# nutzen_03.net
KiCad netlist of a schematic drawn in EAGLE
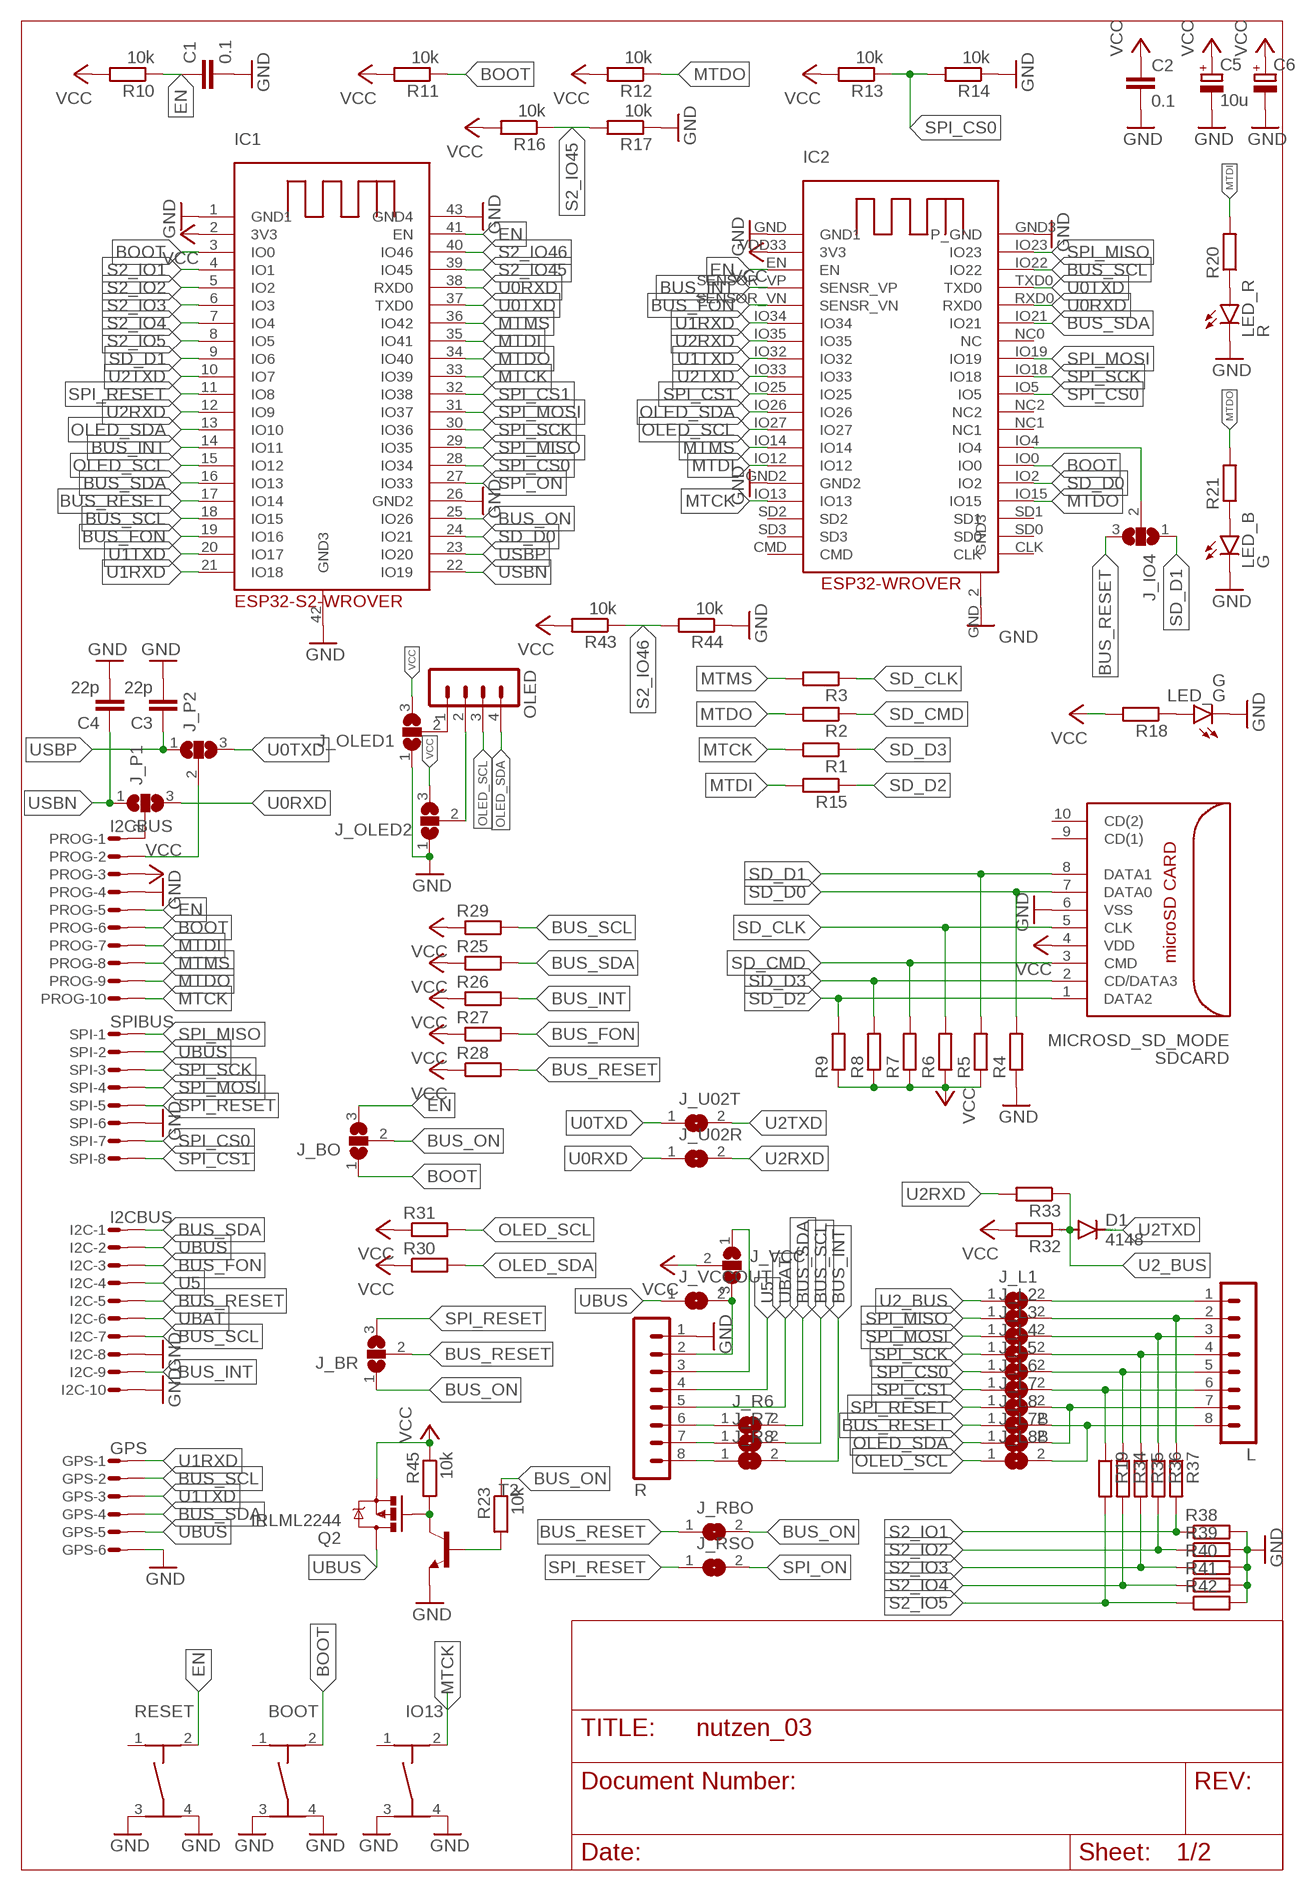
[diagram p0: schematic, sheet 1]

(export (version "E")
  (design (tool "Eeschema 10.0.6"))
  (components
    (comp (ref "BOOT")
      (value "TASTER-9314_SMD")
      (footprint "eagle-import:TASTER-9314_SMD")
      (libsource (lib "eagle-import") (part "TASTER-9314_SMD"))
    )
    (comp (ref "C1")
      (value "0.1")
      (footprint "eagle-import:C0805")
      (libsource (lib "eagle-import") (part "C-EUC0805"))
    )
    (comp (ref "C2")
      (value "0.1")
      (footprint "eagle-import:C0805")
      (libsource (lib "eagle-import") (part "C-EUC0805"))
    )
    (comp (ref "C3")
      (value "22p")
      (footprint "eagle-import:C0805")
      (libsource (lib "eagle-import") (part "C-EUC0805"))
    )
    (comp (ref "C4")
      (value "22p")
      (footprint "eagle-import:C0805")
      (libsource (lib "eagle-import") (part "C-EUC0805"))
    )
    (comp (ref "C5")
      (value "10u")
      (footprint "eagle-import:B_3528-21W")
      (libsource (lib "eagle-import") (part "CPOL-EUB/3528-21W"))
    )
    (comp (ref "C6")
      (value "CPOL-EUC/6032-28R")
      (footprint "eagle-import:C_6032-28R")
      (libsource (lib "eagle-import") (part "CPOL-EUC/6032-28R"))
    )
    (comp (ref "D1")
      (value "4148")
      (footprint "eagle-import:MINIMELF")
      (libsource (lib "eagle-import") (part "DIODE-MINIMELF"))
    )
    (comp (ref "GPS")
      (value "GPS")
      (footprint "eagle-import:MICROMATCH-6SMD")
      (libsource (lib "eagle-import") (part "MICROMATCH-6SMD"))
    )
    (comp (ref "I2C")
      (value "I2CBUS")
      (footprint "eagle-import:MICROMATCH-10SMD")
      (libsource (lib "eagle-import") (part "MICROMATCH-10SMD"))
    )
    (comp (ref "IC1")
      (value "ESP32-S2_WROVER")
      (footprint "eagle-import:ESP32-S2-WROVER")
      (libsource (lib "eagle-import") (part "ESP32-S2_WROVER"))
    )
    (comp (ref "IC2")
      (value "ESP32-WROVER")
      (footprint "eagle-import:ESP32-WROVER")
      (libsource (lib "eagle-import") (part "ESP32-WROVER"))
    )
    (comp (ref "IO13")
      (value "TASTER-9314_SMD")
      (footprint "eagle-import:TASTER-9314_SMD")
      (libsource (lib "eagle-import") (part "TASTER-9314_SMD"))
    )
    (comp (ref "J_BO")
      (value "SJ2W")
      (footprint "eagle-import:SJ_2")
      (libsource (lib "eagle-import") (part "SJ2W"))
    )
    (comp (ref "J_BR")
      (value "SJ2W")
      (footprint "eagle-import:SJ_2")
      (libsource (lib "eagle-import") (part "SJ2W"))
    )
    (comp (ref "J_IO4")
      (value "SJ2W")
      (footprint "eagle-import:SJ_2")
      (libsource (lib "eagle-import") (part "SJ2W"))
    )
    (comp (ref "J_L1")
      (value "SJ")
      (footprint "eagle-import:SJ")
      (libsource (lib "eagle-import") (part "SJ"))
    )
    (comp (ref "J_L2")
      (value "SJ")
      (footprint "eagle-import:SJ")
      (libsource (lib "eagle-import") (part "SJ"))
    )
    (comp (ref "J_L3")
      (value "SJ")
      (footprint "eagle-import:SJ")
      (libsource (lib "eagle-import") (part "SJ"))
    )
    (comp (ref "J_L4")
      (value "SJ")
      (footprint "eagle-import:SJ")
      (libsource (lib "eagle-import") (part "SJ"))
    )
    (comp (ref "J_L5")
      (value "SJ")
      (footprint "eagle-import:SJ")
      (libsource (lib "eagle-import") (part "SJ"))
    )
    (comp (ref "J_L6")
      (value "SJ")
      (footprint "eagle-import:SJ")
      (libsource (lib "eagle-import") (part "SJ"))
    )
    (comp (ref "J_L7")
      (value "SJ")
      (footprint "eagle-import:SJ")
      (libsource (lib "eagle-import") (part "SJ"))
    )
    (comp (ref "J_L7B")
      (value "SJ")
      (footprint "eagle-import:SJ")
      (libsource (lib "eagle-import") (part "SJ"))
    )
    (comp (ref "J_L8")
      (value "SJ")
      (footprint "eagle-import:SJ")
      (libsource (lib "eagle-import") (part "SJ"))
    )
    (comp (ref "J_L8B")
      (value "SJ")
      (footprint "eagle-import:SJ")
      (libsource (lib "eagle-import") (part "SJ"))
    )
    (comp (ref "J_OLED1")
      (value "SJ2W")
      (footprint "eagle-import:SJ_2")
      (libsource (lib "eagle-import") (part "SJ2W"))
    )
    (comp (ref "J_OLED2")
      (value "SJ2W")
      (footprint "eagle-import:SJ_2")
      (libsource (lib "eagle-import") (part "SJ2W"))
    )
    (comp (ref "J_P1")
      (value "SJ2W")
      (footprint "eagle-import:SJ_2")
      (libsource (lib "eagle-import") (part "SJ2W"))
    )
    (comp (ref "J_P2")
      (value "SJ2W")
      (footprint "eagle-import:SJ_2")
      (libsource (lib "eagle-import") (part "SJ2W"))
    )
    (comp (ref "J_R6")
      (value "SJ")
      (footprint "eagle-import:SJ")
      (libsource (lib "eagle-import") (part "SJ"))
    )
    (comp (ref "J_R7")
      (value "SJ")
      (footprint "eagle-import:SJ")
      (libsource (lib "eagle-import") (part "SJ"))
    )
    (comp (ref "J_R8")
      (value "SJ")
      (footprint "eagle-import:SJ")
      (libsource (lib "eagle-import") (part "SJ"))
    )
    (comp (ref "J_RBO")
      (value "SJ")
      (footprint "eagle-import:SJ")
      (libsource (lib "eagle-import") (part "SJ"))
    )
    (comp (ref "J_RSO")
      (value "SJ")
      (footprint "eagle-import:SJ")
      (libsource (lib "eagle-import") (part "SJ"))
    )
    (comp (ref "J_U02R")
      (value "SJ")
      (footprint "eagle-import:SJ")
      (libsource (lib "eagle-import") (part "SJ"))
    )
    (comp (ref "J_U02T")
      (value "SJ")
      (footprint "eagle-import:SJ")
      (libsource (lib "eagle-import") (part "SJ"))
    )
    (comp (ref "J_VCC")
      (value "SJ2W")
      (footprint "eagle-import:SJ_2")
      (libsource (lib "eagle-import") (part "SJ2W"))
    )
    (comp (ref "J_VCCOUT")
      (value "SJ")
      (footprint "eagle-import:SJ")
      (libsource (lib "eagle-import") (part "SJ"))
    )
    (comp (ref "L")
      (value "MA08-1")
      (footprint "eagle-import:MA08-1")
      (libsource (lib "eagle-import") (part "MA08-1"))
    )
    (comp (ref "LED_B")
      (value "G")
      (footprint "eagle-import:CHIPLED_0805")
      (libsource (lib "eagle-import") (part "LEDCHIPLED_0805"))
    )
    (comp (ref "LED_G")
      (value "G")
      (footprint "eagle-import:CHIPLED_0805")
      (libsource (lib "eagle-import") (part "LEDCHIPLED_0805"))
    )
    (comp (ref "LED_R")
      (value "R")
      (footprint "eagle-import:CHIPLED_0805")
      (libsource (lib "eagle-import") (part "LEDCHIPLED_0805"))
    )
    (comp (ref "OLED")
      (value "MA04-1")
      (footprint "eagle-import:MA04-1")
      (libsource (lib "eagle-import") (part "MA04-1"))
    )
    (comp (ref "PROG")
      (value "I2CBUS")
      (footprint "eagle-import:MICROMATCH-10SMD")
      (libsource (lib "eagle-import") (part "MICROMATCH-10SMD"))
    )
    (comp (ref "Q2")
      (value "IRLML2244")
      (footprint "eagle-import:SOT23-3")
      (libsource (lib "eagle-import") (part "MOSFET-PCHANNELIRLML2244"))
    )
    (comp (ref "R")
      (value "MA08-1")
      (footprint "eagle-import:MA08-1")
      (libsource (lib "eagle-import") (part "MA08-1"))
    )
    (comp (ref "R1")
      (value "R-EU_R0805")
      (footprint "eagle-import:R0805")
      (libsource (lib "eagle-import") (part "R-EU_R0805"))
    )
    (comp (ref "R2")
      (value "R-EU_R0805")
      (footprint "eagle-import:R0805")
      (libsource (lib "eagle-import") (part "R-EU_R0805"))
    )
    (comp (ref "R3")
      (value "R-EU_R0805")
      (footprint "eagle-import:R0805")
      (libsource (lib "eagle-import") (part "R-EU_R0805"))
    )
    (comp (ref "R4")
      (value "R-EU_R0805")
      (footprint "eagle-import:R0805")
      (libsource (lib "eagle-import") (part "R-EU_R0805"))
    )
    (comp (ref "R5")
      (value "R-EU_R0805")
      (footprint "eagle-import:R0805")
      (libsource (lib "eagle-import") (part "R-EU_R0805"))
    )
    (comp (ref "R6")
      (value "R-EU_R0805")
      (footprint "eagle-import:R0805")
      (libsource (lib "eagle-import") (part "R-EU_R0805"))
    )
    (comp (ref "R7")
      (value "R-EU_R0805")
      (footprint "eagle-import:R0805")
      (libsource (lib "eagle-import") (part "R-EU_R0805"))
    )
    (comp (ref "R8")
      (value "R-EU_R0805")
      (footprint "eagle-import:R0805")
      (libsource (lib "eagle-import") (part "R-EU_R0805"))
    )
    (comp (ref "R9")
      (value "R-EU_R0805")
      (footprint "eagle-import:R0805")
      (libsource (lib "eagle-import") (part "R-EU_R0805"))
    )
    (comp (ref "R10")
      (value "10k")
      (footprint "eagle-import:R0805")
      (libsource (lib "eagle-import") (part "R-EU_R0805"))
    )
    (comp (ref "R11")
      (value "10k")
      (footprint "eagle-import:R0805")
      (libsource (lib "eagle-import") (part "R-EU_R0805"))
    )
    (comp (ref "R12")
      (value "10k")
      (footprint "eagle-import:R0805")
      (libsource (lib "eagle-import") (part "R-EU_R0805"))
    )
    (comp (ref "R13")
      (value "10k")
      (footprint "eagle-import:R0805")
      (libsource (lib "eagle-import") (part "R-EU_R0805"))
    )
    (comp (ref "R14")
      (value "10k")
      (footprint "eagle-import:R0805")
      (libsource (lib "eagle-import") (part "R-EU_R0805"))
    )
    (comp (ref "R15")
      (value "R-EU_R0805")
      (footprint "eagle-import:R0805")
      (libsource (lib "eagle-import") (part "R-EU_R0805"))
    )
    (comp (ref "R16")
      (value "10k")
      (footprint "eagle-import:R0805")
      (libsource (lib "eagle-import") (part "R-EU_R0805"))
    )
    (comp (ref "R17")
      (value "10k")
      (footprint "eagle-import:R0805")
      (libsource (lib "eagle-import") (part "R-EU_R0805"))
    )
    (comp (ref "R18")
      (value "R-EU_R0603")
      (footprint "eagle-import:R0603")
      (libsource (lib "eagle-import") (part "R-EU_R0603"))
    )
    (comp (ref "R19")
      (value "R-EU_R0805")
      (footprint "eagle-import:R0805")
      (libsource (lib "eagle-import") (part "R-EU_R0805"))
    )
    (comp (ref "R20")
      (value "R-EU_R0603")
      (footprint "eagle-import:R0603")
      (libsource (lib "eagle-import") (part "R-EU_R0603"))
    )
    (comp (ref "R21")
      (value "R-EU_R0603")
      (footprint "eagle-import:R0603")
      (libsource (lib "eagle-import") (part "R-EU_R0603"))
    )
    (comp (ref "R23")
      (value "10k")
      (footprint "eagle-import:R0805")
      (libsource (lib "eagle-import") (part "R-EU_R0805"))
    )
    (comp (ref "R25")
      (value "R-EU_R0805")
      (footprint "eagle-import:R0805")
      (libsource (lib "eagle-import") (part "R-EU_R0805"))
    )
    (comp (ref "R26")
      (value "R-EU_R0805")
      (footprint "eagle-import:R0805")
      (libsource (lib "eagle-import") (part "R-EU_R0805"))
    )
    (comp (ref "R27")
      (value "R-EU_R0805")
      (footprint "eagle-import:R0805")
      (libsource (lib "eagle-import") (part "R-EU_R0805"))
    )
    (comp (ref "R28")
      (value "R-EU_R0805")
      (footprint "eagle-import:R0805")
      (libsource (lib "eagle-import") (part "R-EU_R0805"))
    )
    (comp (ref "R29")
      (value "R-EU_R0805")
      (footprint "eagle-import:R0805")
      (libsource (lib "eagle-import") (part "R-EU_R0805"))
    )
    (comp (ref "R30")
      (value "R-EU_R0805")
      (footprint "eagle-import:R0805")
      (libsource (lib "eagle-import") (part "R-EU_R0805"))
    )
    (comp (ref "R31")
      (value "R-EU_R0805")
      (footprint "eagle-import:R0805")
      (libsource (lib "eagle-import") (part "R-EU_R0805"))
    )
    (comp (ref "R32")
      (value "R-EU_R0805")
      (footprint "eagle-import:R0805")
      (libsource (lib "eagle-import") (part "R-EU_R0805"))
    )
    (comp (ref "R33")
      (value "R-EU_R0805")
      (footprint "eagle-import:R0805")
      (libsource (lib "eagle-import") (part "R-EU_R0805"))
    )
    (comp (ref "R34")
      (value "R-EU_R0805")
      (footprint "eagle-import:R0805")
      (libsource (lib "eagle-import") (part "R-EU_R0805"))
    )
    (comp (ref "R35")
      (value "R-EU_R0805")
      (footprint "eagle-import:R0805")
      (libsource (lib "eagle-import") (part "R-EU_R0805"))
    )
    (comp (ref "R36")
      (value "R-EU_R0805")
      (footprint "eagle-import:R0805")
      (libsource (lib "eagle-import") (part "R-EU_R0805"))
    )
    (comp (ref "R37")
      (value "R-EU_R0805")
      (footprint "eagle-import:R0805")
      (libsource (lib "eagle-import") (part "R-EU_R0805"))
    )
    (comp (ref "R38")
      (value "R-EU_R0805")
      (footprint "eagle-import:R0805")
      (libsource (lib "eagle-import") (part "R-EU_R0805"))
    )
    (comp (ref "R39")
      (value "R-EU_R0805")
      (footprint "eagle-import:R0805")
      (libsource (lib "eagle-import") (part "R-EU_R0805"))
    )
    (comp (ref "R40")
      (value "R-EU_R0805")
      (footprint "eagle-import:R0805")
      (libsource (lib "eagle-import") (part "R-EU_R0805"))
    )
    (comp (ref "R41")
      (value "R-EU_R0805")
      (footprint "eagle-import:R0805")
      (libsource (lib "eagle-import") (part "R-EU_R0805"))
    )
    (comp (ref "R42")
      (value "R-EU_R0805")
      (footprint "eagle-import:R0805")
      (libsource (lib "eagle-import") (part "R-EU_R0805"))
    )
    (comp (ref "R43")
      (value "10k")
      (footprint "eagle-import:R0805")
      (libsource (lib "eagle-import") (part "R-EU_R0805"))
    )
    (comp (ref "R44")
      (value "10k")
      (footprint "eagle-import:R0805")
      (libsource (lib "eagle-import") (part "R-EU_R0805"))
    )
    (comp (ref "R45")
      (value "10k")
      (footprint "eagle-import:R0805")
      (libsource (lib "eagle-import") (part "R-EU_R0805"))
    )
    (comp (ref "RESET")
      (value "TASTER-9314_SMD")
      (footprint "eagle-import:TASTER-9314_SMD")
      (libsource (lib "eagle-import") (part "TASTER-9314_SMD"))
    )
    (comp (ref "SDCARD")
      (value "MICROSD_SD_MODE")
      (footprint "eagle-import:MICRO_SD_CONNECTOR")
      (libsource (lib "eagle-import") (part "MICROSD_SD_MODE"))
    )
    (comp (ref "SPI")
      (value "SPIBUS")
      (footprint "eagle-import:MICROMATCH-8-SMD")
      (libsource (lib "eagle-import") (part "MICROMATCH-8SMD"))
    )
    (comp (ref "T2")
      (value "BC817-16-NPN-SOT23-BEC")
      (footprint "eagle-import:SOT23-BEC")
      (libsource (lib "eagle-import") (part "-NPN-SOT23-BECBC817-16"))
    )
  )
  (nets
    (net (code "1") (name "BOOT") (class "Default")
      (node (ref "BOOT") (pin "2") (pinfunction "2_2") (pintype "passive"))
      (node (ref "IC1") (pin "3") (pinfunction "IO0_3") (pintype "bidirectional"))
      (node (ref "IC2") (pin "IO0") (pinfunction "IO0_IO0") (pintype "bidirectional"))
      (node (ref "J_BO") (pin "1") (pinfunction "1_1") (pintype "passive"))
      (node (ref "PROG") (pin "6") (pinfunction "S_6") (pintype "passive"))
      (node (ref "R11") (pin "1") (pinfunction "1_1") (pintype "passive"))
    )
    (net (code "2") (name "BUS_FON") (class "Default")
      (node (ref "I2C") (pin "3") (pinfunction "S_3") (pintype "passive"))
      (node (ref "IC1") (pin "19") (pinfunction "IO16_19") (pintype "bidirectional"))
      (node (ref "IC2") (pin "SENSOR_VN") (pinfunction "SENSR_VN_SENSOR_VN") (pintype "bidirectional"))
      (node (ref "R27") (pin "2") (pinfunction "2_2") (pintype "passive"))
    )
    (net (code "3") (name "BUS_INT") (class "Default")
      (node (ref "I2C") (pin "9") (pinfunction "S_9") (pintype "passive"))
      (node (ref "IC1") (pin "14") (pinfunction "IO11_14") (pintype "bidirectional"))
      (node (ref "IC2") (pin "SENSOR_VP") (pinfunction "SENSR_VP_SENSOR_VP") (pintype "bidirectional"))
      (node (ref "J_R8") (pin "2") (pinfunction "2_2") (pintype "passive"))
      (node (ref "R26") (pin "2") (pinfunction "2_2") (pintype "passive"))
    )
    (net (code "4") (name "BUS_ON") (class "Default")
      (node (ref "IC1") (pin "25") (pinfunction "IO26_25") (pintype "bidirectional"))
      (node (ref "J_BO") (pin "2") (pinfunction "2_2") (pintype "passive"))
      (node (ref "J_BR") (pin "1") (pinfunction "1_1") (pintype "passive"))
      (node (ref "J_RBO") (pin "2") (pinfunction "2_2") (pintype "passive"))
      (node (ref "R23") (pin "1") (pinfunction "1_1") (pintype "passive"))
    )
    (net (code "5") (name "BUS_RESET") (class "Default")
      (node (ref "I2C") (pin "5") (pinfunction "S_5") (pintype "passive"))
      (node (ref "IC1") (pin "17") (pinfunction "IO14_17") (pintype "bidirectional"))
      (node (ref "J_BR") (pin "2") (pinfunction "2_2") (pintype "passive"))
      (node (ref "J_IO4") (pin "3") (pinfunction "3_3") (pintype "passive"))
      (node (ref "J_L8") (pin "1") (pinfunction "1_1") (pintype "passive"))
      (node (ref "J_RBO") (pin "1") (pinfunction "1_1") (pintype "passive"))
      (node (ref "R28") (pin "2") (pinfunction "2_2") (pintype "passive"))
    )
    (net (code "6") (name "BUS_SCL") (class "Default")
      (node (ref "GPS") (pin "2") (pinfunction "S_2") (pintype "passive"))
      (node (ref "I2C") (pin "7") (pinfunction "S_7") (pintype "passive"))
      (node (ref "IC1") (pin "18") (pinfunction "IO15_18") (pintype "bidirectional"))
      (node (ref "IC2") (pin "IO22") (pinfunction "IO22_IO22") (pintype "bidirectional"))
      (node (ref "J_R7") (pin "2") (pinfunction "2_2") (pintype "passive"))
      (node (ref "R29") (pin "2") (pinfunction "2_2") (pintype "passive"))
    )
    (net (code "7") (name "BUS_SDA") (class "Default")
      (node (ref "GPS") (pin "4") (pinfunction "S_4") (pintype "passive"))
      (node (ref "I2C") (pin "1") (pinfunction "S_1") (pintype "passive"))
      (node (ref "IC1") (pin "16") (pinfunction "IO13_16") (pintype "bidirectional"))
      (node (ref "IC2") (pin "IO21") (pinfunction "IO21_IO21") (pintype "bidirectional"))
      (node (ref "J_R6") (pin "2") (pinfunction "2_2") (pintype "passive"))
      (node (ref "R25") (pin "2") (pinfunction "2_2") (pintype "passive"))
    )
    (net (code "8") (name "EN") (class "Default")
      (node (ref "C1") (pin "1") (pinfunction "1_1") (pintype "passive"))
      (node (ref "IC1") (pin "41") (pinfunction "EN_41") (pintype "input"))
      (node (ref "IC2") (pin "EN") (pinfunction "EN_EN") (pintype "bidirectional"))
      (node (ref "J_BO") (pin "3") (pinfunction "3_3") (pintype "passive"))
      (node (ref "PROG") (pin "5") (pinfunction "S_5") (pintype "passive"))
      (node (ref "R10") (pin "1") (pinfunction "1_1") (pintype "passive"))
      (node (ref "RESET") (pin "2") (pinfunction "2_2") (pintype "passive"))
    )
    (net (code "9") (name "GND") (class "Default")
      (node (ref "BOOT") (pin "3") (pinfunction "3_3") (pintype "passive"))
      (node (ref "BOOT") (pin "4") (pinfunction "4_4") (pintype "passive"))
      (node (ref "C1") (pin "2") (pinfunction "2_2") (pintype "passive"))
      (node (ref "C2") (pin "2") (pinfunction "2_2") (pintype "passive"))
      (node (ref "C3") (pin "2") (pinfunction "2_2") (pintype "passive"))
      (node (ref "C4") (pin "2") (pinfunction "2_2") (pintype "passive"))
      (node (ref "C5") (pin "-") (pinfunction "-_-") (pintype "passive"))
      (node (ref "C6") (pin "-") (pinfunction "-_-") (pintype "passive"))
      (node (ref "GPS") (pin "6") (pinfunction "S_6") (pintype "passive"))
      (node (ref "I2C") (pin "10") (pinfunction "S_10") (pintype "passive"))
      (node (ref "I2C") (pin "8") (pinfunction "S_8") (pintype "passive"))
      (node (ref "IC1") (pin "1") (pinfunction "GND1_1") (pintype "passive"))
      (node (ref "IC1") (pin "26") (pinfunction "GND2_26") (pintype "passive"))
      (node (ref "IC1") (pin "42") (pinfunction "GND3_42") (pintype "passive"))
      (node (ref "IC1") (pin "43") (pinfunction "GND4_43") (pintype "passive"))
      (node (ref "IC2") (pin "GND") (pinfunction "GND1_GND") (pintype "bidirectional"))
      (node (ref "IC2") (pin "GND2") (pinfunction "GND2_GND2") (pintype "bidirectional"))
      (node (ref "IC2") (pin "GND3") (pinfunction "P_GND_GND3") (pintype "bidirectional"))
      (node (ref "IC2") (pin "GND_2") (pinfunction "GND3_GND_2") (pintype "bidirectional"))
      (node (ref "IO13") (pin "3") (pinfunction "3_3") (pintype "passive"))
      (node (ref "IO13") (pin "4") (pinfunction "4_4") (pintype "passive"))
      (node (ref "J_OLED1") (pin "1") (pinfunction "1_1") (pintype "passive"))
      (node (ref "J_OLED2") (pin "1") (pinfunction "1_1") (pintype "passive"))
      (node (ref "LED_B") (pin "C") (pinfunction "C_C") (pintype "passive"))
      (node (ref "LED_G") (pin "C") (pinfunction "C_C") (pintype "passive"))
      (node (ref "LED_R") (pin "C") (pinfunction "C_C") (pintype "passive"))
      (node (ref "PROG") (pin "4") (pinfunction "S_4") (pintype "passive"))
      (node (ref "R") (pin "1") (pinfunction "1_1") (pintype "passive"))
      (node (ref "R14") (pin "1") (pinfunction "1_1") (pintype "passive"))
      (node (ref "R17") (pin "1") (pinfunction "1_1") (pintype "passive"))
      (node (ref "R38") (pin "2") (pinfunction "2_2") (pintype "passive"))
      (node (ref "R39") (pin "2") (pinfunction "2_2") (pintype "passive"))
      (node (ref "R4") (pin "1") (pinfunction "1_1") (pintype "passive"))
      (node (ref "R40") (pin "2") (pinfunction "2_2") (pintype "passive"))
      (node (ref "R41") (pin "2") (pinfunction "2_2") (pintype "passive"))
      (node (ref "R42") (pin "2") (pinfunction "2_2") (pintype "passive"))
      (node (ref "R44") (pin "1") (pinfunction "1_1") (pintype "passive"))
      (node (ref "RESET") (pin "3") (pinfunction "3_3") (pintype "passive"))
      (node (ref "RESET") (pin "4") (pinfunction "4_4") (pintype "passive"))
      (node (ref "SDCARD") (pin "6") (pinfunction "VSS_6") (pintype "bidirectional"))
      (node (ref "SPI") (pin "6") (pinfunction "S_6") (pintype "passive"))
      (node (ref "T2") (pin "E") (pinfunction "E_E") (pintype "passive"))
    )
    (net (code "10") (name "MTCK") (class "Default")
      (node (ref "IC1") (pin "33") (pinfunction "IO39_33") (pintype "bidirectional"))
      (node (ref "IC2") (pin "IO13") (pinfunction "IO13_IO13") (pintype "bidirectional"))
      (node (ref "IO13") (pin "2") (pinfunction "2_2") (pintype "passive"))
      (node (ref "PROG") (pin "10") (pinfunction "S_10") (pintype "passive"))
      (node (ref "R1") (pin "2") (pinfunction "2_2") (pintype "passive"))
    )
    (net (code "11") (name "MTDI") (class "Default")
      (node (ref "IC1") (pin "35") (pinfunction "IO41_35") (pintype "bidirectional"))
      (node (ref "IC2") (pin "IO12") (pinfunction "IO12_IO12") (pintype "bidirectional"))
      (node (ref "PROG") (pin "7") (pinfunction "S_7") (pintype "passive"))
      (node (ref "R15") (pin "2") (pinfunction "2_2") (pintype "passive"))
      (node (ref "R20") (pin "2") (pinfunction "2_2") (pintype "passive"))
    )
    (net (code "12") (name "MTDO") (class "Default")
      (node (ref "IC1") (pin "34") (pinfunction "IO40_34") (pintype "bidirectional"))
      (node (ref "IC2") (pin "IO15") (pinfunction "IO15_IO15") (pintype "bidirectional"))
      (node (ref "PROG") (pin "9") (pinfunction "S_9") (pintype "passive"))
      (node (ref "R12") (pin "1") (pinfunction "1_1") (pintype "passive"))
      (node (ref "R2") (pin "2") (pinfunction "2_2") (pintype "passive"))
      (node (ref "R21") (pin "2") (pinfunction "2_2") (pintype "passive"))
    )
    (net (code "13") (name "MTMS") (class "Default")
      (node (ref "IC1") (pin "36") (pinfunction "IO42_36") (pintype "bidirectional"))
      (node (ref "IC2") (pin "IO14") (pinfunction "IO14_IO14") (pintype "bidirectional"))
      (node (ref "PROG") (pin "8") (pinfunction "S_8") (pintype "passive"))
      (node (ref "R3") (pin "2") (pinfunction "2_2") (pintype "passive"))
    )
    (net (code "14") (name "Net-(IC2-PadIO4)") (class "Default")
      (node (ref "IC2") (pin "IO4") (pinfunction "IO4_IO4") (pintype "bidirectional"))
      (node (ref "J_IO4") (pin "2") (pinfunction "2_2") (pintype "passive"))
    )
    (net (code "15") (name "Net-(J_L1-Pad2)") (class "Default")
      (node (ref "J_L1") (pin "2") (pinfunction "2_2") (pintype "passive"))
      (node (ref "L") (pin "1") (pinfunction "1_1") (pintype "passive"))
    )
    (net (code "16") (name "Net-(J_L2-Pad2)") (class "Default")
      (node (ref "J_L2") (pin "2") (pinfunction "2_2") (pintype "passive"))
      (node (ref "L") (pin "2") (pinfunction "2_2") (pintype "passive"))
      (node (ref "R37") (pin "1") (pinfunction "1_1") (pintype "passive"))
    )
    (net (code "17") (name "Net-(J_L3-Pad2)") (class "Default")
      (node (ref "J_L3") (pin "2") (pinfunction "2_2") (pintype "passive"))
      (node (ref "L") (pin "3") (pinfunction "3_3") (pintype "passive"))
      (node (ref "R36") (pin "1") (pinfunction "1_1") (pintype "passive"))
    )
    (net (code "18") (name "Net-(J_L4-Pad2)") (class "Default")
      (node (ref "J_L4") (pin "2") (pinfunction "2_2") (pintype "passive"))
      (node (ref "L") (pin "4") (pinfunction "4_4") (pintype "passive"))
      (node (ref "R35") (pin "1") (pinfunction "1_1") (pintype "passive"))
    )
    (net (code "19") (name "Net-(J_L5-Pad2)") (class "Default")
      (node (ref "J_L5") (pin "2") (pinfunction "2_2") (pintype "passive"))
      (node (ref "L") (pin "5") (pinfunction "5_5") (pintype "passive"))
      (node (ref "R34") (pin "1") (pinfunction "1_1") (pintype "passive"))
    )
    (net (code "20") (name "Net-(J_L6-Pad2)") (class "Default")
      (node (ref "J_L6") (pin "2") (pinfunction "2_2") (pintype "passive"))
      (node (ref "L") (pin "6") (pinfunction "6_6") (pintype "passive"))
      (node (ref "R19") (pin "1") (pinfunction "1_1") (pintype "passive"))
    )
    (net (code "21") (name "Net-(J_L7-Pad2)") (class "Default")
      (node (ref "J_L7") (pin "2") (pinfunction "2_2") (pintype "passive"))
      (node (ref "J_L7B") (pin "2") (pinfunction "2_2") (pintype "passive"))
      (node (ref "L") (pin "7") (pinfunction "7_7") (pintype "passive"))
    )
    (net (code "22") (name "Net-(J_L8-Pad2)") (class "Default")
      (node (ref "J_L8") (pin "2") (pinfunction "2_2") (pintype "passive"))
      (node (ref "J_L8B") (pin "2") (pinfunction "2_2") (pintype "passive"))
      (node (ref "L") (pin "8") (pinfunction "8_8") (pintype "passive"))
    )
    (net (code "23") (name "Net-(J_OLED1-Pad2)") (class "Default")
      (node (ref "J_OLED1") (pin "2") (pinfunction "2_2") (pintype "passive"))
      (node (ref "OLED") (pin "1") (pinfunction "1_1") (pintype "passive"))
    )
    (net (code "24") (name "Net-(J_OLED2-Pad2)") (class "Default")
      (node (ref "J_OLED2") (pin "2") (pinfunction "2_2") (pintype "passive"))
      (node (ref "OLED") (pin "2") (pinfunction "2_2") (pintype "passive"))
    )
    (net (code "25") (name "Net-(J_R6-Pad1)") (class "Default")
      (node (ref "J_R6") (pin "1") (pinfunction "1_1") (pintype "passive"))
      (node (ref "R") (pin "6") (pinfunction "6_6") (pintype "passive"))
    )
    (net (code "26") (name "Net-(J_R7-Pad1)") (class "Default")
      (node (ref "J_R7") (pin "1") (pinfunction "1_1") (pintype "passive"))
      (node (ref "R") (pin "7") (pinfunction "7_7") (pintype "passive"))
    )
    (net (code "27") (name "Net-(J_R8-Pad1)") (class "Default")
      (node (ref "J_R8") (pin "1") (pinfunction "1_1") (pintype "passive"))
      (node (ref "R") (pin "8") (pinfunction "8_8") (pintype "passive"))
    )
    (net (code "28") (name "Net-(J_VCC-Pad1)") (class "Default")
      (node (ref "J_VCC") (pin "1") (pinfunction "1_1") (pintype "passive"))
      (node (ref "R") (pin "3") (pinfunction "3_3") (pintype "passive"))
    )
    (net (code "29") (name "Net-(J_VCC-Pad3)") (class "Default")
      (node (ref "J_VCC") (pin "3") (pinfunction "3_3") (pintype "passive"))
      (node (ref "J_VCCOUT") (pin "2") (pinfunction "2_2") (pintype "passive"))
      (node (ref "R") (pin "2") (pinfunction "2_2") (pintype "passive"))
    )
    (net (code "30") (name "Net-(LED_B-PadA)") (class "Default")
      (node (ref "LED_B") (pin "A") (pinfunction "A_A") (pintype "passive"))
      (node (ref "R21") (pin "1") (pinfunction "1_1") (pintype "passive"))
    )
    (net (code "31") (name "Net-(LED_G-PadA)") (class "Default")
      (node (ref "LED_G") (pin "A") (pinfunction "A_A") (pintype "passive"))
      (node (ref "R18") (pin "1") (pinfunction "1_1") (pintype "passive"))
    )
    (net (code "32") (name "Net-(LED_R-PadA)") (class "Default")
      (node (ref "LED_R") (pin "A") (pinfunction "A_A") (pintype "passive"))
      (node (ref "R20") (pin "1") (pinfunction "1_1") (pintype "passive"))
    )
    (net (code "33") (name "Net-(PROGA-S)") (class "Default")
      (node (ref "J_P1") (pin "2") (pinfunction "2_2") (pintype "passive"))
      (node (ref "PROG") (pin "1") (pinfunction "S_1") (pintype "passive"))
    )
    (net (code "34") (name "Net-(PROGC-S)") (class "Default")
      (node (ref "J_P2") (pin "2") (pinfunction "2_2") (pintype "passive"))
      (node (ref "PROG") (pin "2") (pinfunction "S_2") (pintype "passive"))
    )
    (net (code "35") (name "Net-(Q2-G)") (class "Default")
      (node (ref "Q2") (pin "1") (pinfunction "G_1") (pintype "passive"))
      (node (ref "R45") (pin "2") (pinfunction "2_2") (pintype "passive"))
      (node (ref "T2") (pin "C") (pinfunction "C_C") (pintype "passive"))
    )
    (net (code "36") (name "Net-(R23-Pad2)") (class "Default")
      (node (ref "R23") (pin "2") (pinfunction "2_2") (pintype "passive"))
      (node (ref "T2") (pin "B") (pinfunction "B_B") (pintype "passive"))
    )
    (net (code "37") (name "OLED_SCL") (class "Default")
      (node (ref "IC1") (pin "15") (pinfunction "IO12_15") (pintype "bidirectional"))
      (node (ref "IC2") (pin "IO27") (pinfunction "IO27_IO27") (pintype "bidirectional"))
      (node (ref "J_L8B") (pin "1") (pinfunction "1_1") (pintype "passive"))
      (node (ref "OLED") (pin "3") (pinfunction "3_3") (pintype "passive"))
      (node (ref "R31") (pin "2") (pinfunction "2_2") (pintype "passive"))
    )
    (net (code "38") (name "OLED_SDA") (class "Default")
      (node (ref "IC1") (pin "13") (pinfunction "IO10_13") (pintype "bidirectional"))
      (node (ref "IC2") (pin "IO26") (pinfunction "IO26_IO26") (pintype "bidirectional"))
      (node (ref "J_L7B") (pin "1") (pinfunction "1_1") (pintype "passive"))
      (node (ref "OLED") (pin "4") (pinfunction "4_4") (pintype "passive"))
      (node (ref "R30") (pin "2") (pinfunction "2_2") (pintype "passive"))
    )
    (net (code "39") (name "S2_IO1") (class "Default")
      (node (ref "IC1") (pin "4") (pinfunction "IO1_4") (pintype "bidirectional"))
      (node (ref "R37") (pin "2") (pinfunction "2_2") (pintype "passive"))
      (node (ref "R38") (pin "1") (pinfunction "1_1") (pintype "passive"))
    )
    (net (code "40") (name "S2_IO2") (class "Default")
      (node (ref "IC1") (pin "5") (pinfunction "IO2_5") (pintype "bidirectional"))
      (node (ref "R36") (pin "2") (pinfunction "2_2") (pintype "passive"))
      (node (ref "R39") (pin "1") (pinfunction "1_1") (pintype "passive"))
    )
    (net (code "41") (name "S2_IO3") (class "Default")
      (node (ref "IC1") (pin "6") (pinfunction "IO3_6") (pintype "bidirectional"))
      (node (ref "R35") (pin "2") (pinfunction "2_2") (pintype "passive"))
      (node (ref "R40") (pin "1") (pinfunction "1_1") (pintype "passive"))
    )
    (net (code "42") (name "S2_IO4") (class "Default")
      (node (ref "IC1") (pin "7") (pinfunction "IO4_7") (pintype "bidirectional"))
      (node (ref "R34") (pin "2") (pinfunction "2_2") (pintype "passive"))
      (node (ref "R41") (pin "1") (pinfunction "1_1") (pintype "passive"))
    )
    (net (code "43") (name "S2_IO5") (class "Default")
      (node (ref "IC1") (pin "8") (pinfunction "IO5_8") (pintype "bidirectional"))
      (node (ref "R19") (pin "2") (pinfunction "2_2") (pintype "passive"))
      (node (ref "R42") (pin "1") (pinfunction "1_1") (pintype "passive"))
    )
    (net (code "44") (name "S2_IO45") (class "Default")
      (node (ref "IC1") (pin "39") (pinfunction "IO45_39") (pintype "bidirectional"))
      (node (ref "R16") (pin "1") (pinfunction "1_1") (pintype "passive"))
      (node (ref "R17") (pin "2") (pinfunction "2_2") (pintype "passive"))
    )
    (net (code "45") (name "S2_IO46") (class "Default")
      (node (ref "IC1") (pin "40") (pinfunction "IO46_40") (pintype "bidirectional"))
      (node (ref "R43") (pin "1") (pinfunction "1_1") (pintype "passive"))
      (node (ref "R44") (pin "2") (pinfunction "2_2") (pintype "passive"))
    )
    (net (code "46") (name "SD_CLK") (class "Default")
      (node (ref "R3") (pin "1") (pinfunction "1_1") (pintype "passive"))
      (node (ref "R6") (pin "2") (pinfunction "2_2") (pintype "passive"))
      (node (ref "SDCARD") (pin "5") (pinfunction "CLK_5") (pintype "bidirectional"))
    )
    (net (code "47") (name "SD_CMD") (class "Default")
      (node (ref "R2") (pin "1") (pinfunction "1_1") (pintype "passive"))
      (node (ref "R7") (pin "2") (pinfunction "2_2") (pintype "passive"))
      (node (ref "SDCARD") (pin "3") (pinfunction "CMD_3") (pintype "bidirectional"))
    )
    (net (code "48") (name "SD_D0") (class "Default")
      (node (ref "IC1") (pin "24") (pinfunction "IO21_24") (pintype "bidirectional"))
      (node (ref "IC2") (pin "IO2") (pinfunction "IO2_IO2") (pintype "bidirectional"))
      (node (ref "R4") (pin "2") (pinfunction "2_2") (pintype "passive"))
      (node (ref "SDCARD") (pin "7") (pinfunction "DATA0_7") (pintype "bidirectional"))
    )
    (net (code "49") (name "SD_D1") (class "Default")
      (node (ref "IC1") (pin "9") (pinfunction "IO6_9") (pintype "bidirectional"))
      (node (ref "J_IO4") (pin "1") (pinfunction "1_1") (pintype "passive"))
      (node (ref "R5") (pin "2") (pinfunction "2_2") (pintype "passive"))
      (node (ref "SDCARD") (pin "8") (pinfunction "DATA1_8") (pintype "bidirectional"))
    )
    (net (code "50") (name "SD_D2") (class "Default")
      (node (ref "R15") (pin "1") (pinfunction "1_1") (pintype "passive"))
      (node (ref "R9") (pin "2") (pinfunction "2_2") (pintype "passive"))
      (node (ref "SDCARD") (pin "1") (pinfunction "DATA2_1") (pintype "bidirectional"))
    )
    (net (code "51") (name "SD_D3") (class "Default")
      (node (ref "R1") (pin "1") (pinfunction "1_1") (pintype "passive"))
      (node (ref "R8") (pin "2") (pinfunction "2_2") (pintype "passive"))
      (node (ref "SDCARD") (pin "2") (pinfunction "CD/DATA3_2") (pintype "bidirectional"))
    )
    (net (code "52") (name "SPI_CS0") (class "Default")
      (node (ref "IC1") (pin "28") (pinfunction "IO34_28") (pintype "bidirectional"))
      (node (ref "IC2") (pin "IO5") (pinfunction "IO5_IO5") (pintype "bidirectional"))
      (node (ref "J_L5") (pin "1") (pinfunction "1_1") (pintype "passive"))
      (node (ref "R13") (pin "1") (pinfunction "1_1") (pintype "passive"))
      (node (ref "R14") (pin "2") (pinfunction "2_2") (pintype "passive"))
      (node (ref "SPI") (pin "7") (pinfunction "S_7") (pintype "passive"))
    )
    (net (code "53") (name "SPI_CS1") (class "Default")
      (node (ref "IC1") (pin "32") (pinfunction "IO38_32") (pintype "bidirectional"))
      (node (ref "IC2") (pin "IO25") (pinfunction "IO25_IO25") (pintype "bidirectional"))
      (node (ref "J_L6") (pin "1") (pinfunction "1_1") (pintype "passive"))
      (node (ref "SPI") (pin "8") (pinfunction "S_8") (pintype "passive"))
    )
    (net (code "54") (name "SPI_MISO") (class "Default")
      (node (ref "IC1") (pin "29") (pinfunction "IO35_29") (pintype "bidirectional"))
      (node (ref "IC2") (pin "IO23") (pinfunction "IO23_IO23") (pintype "bidirectional"))
      (node (ref "J_L2") (pin "1") (pinfunction "1_1") (pintype "passive"))
      (node (ref "SPI") (pin "1") (pinfunction "S_1") (pintype "passive"))
    )
    (net (code "55") (name "SPI_MOSI") (class "Default")
      (node (ref "IC1") (pin "31") (pinfunction "IO37_31") (pintype "bidirectional"))
      (node (ref "IC2") (pin "IO19") (pinfunction "IO19_IO19") (pintype "bidirectional"))
      (node (ref "J_L3") (pin "1") (pinfunction "1_1") (pintype "passive"))
      (node (ref "SPI") (pin "4") (pinfunction "S_4") (pintype "passive"))
    )
    (net (code "56") (name "SPI_ON") (class "Default")
      (node (ref "IC1") (pin "27") (pinfunction "IO33_27") (pintype "bidirectional"))
      (node (ref "J_RSO") (pin "2") (pinfunction "2_2") (pintype "passive"))
    )
    (net (code "57") (name "SPI_RESET") (class "Default")
      (node (ref "IC1") (pin "11") (pinfunction "IO8_11") (pintype "bidirectional"))
      (node (ref "J_BR") (pin "3") (pinfunction "3_3") (pintype "passive"))
      (node (ref "J_L7") (pin "1") (pinfunction "1_1") (pintype "passive"))
      (node (ref "J_RSO") (pin "1") (pinfunction "1_1") (pintype "passive"))
      (node (ref "SPI") (pin "5") (pinfunction "S_5") (pintype "passive"))
    )
    (net (code "58") (name "SPI_SCK") (class "Default")
      (node (ref "IC1") (pin "30") (pinfunction "IO36_30") (pintype "bidirectional"))
      (node (ref "IC2") (pin "IO18") (pinfunction "IO18_IO18") (pintype "bidirectional"))
      (node (ref "J_L4") (pin "1") (pinfunction "1_1") (pintype "passive"))
      (node (ref "SPI") (pin "3") (pinfunction "S_3") (pintype "passive"))
    )
    (net (code "59") (name "U0RXD") (class "Default")
      (node (ref "IC1") (pin "38") (pinfunction "RXD0_38") (pintype "input"))
      (node (ref "IC2") (pin "RXD0") (pinfunction "RXD0_RXD0") (pintype "bidirectional"))
      (node (ref "J_P1") (pin "3") (pinfunction "3_3") (pintype "passive"))
      (node (ref "J_U02R") (pin "1") (pinfunction "1_1") (pintype "passive"))
    )
    (net (code "60") (name "U0TXD") (class "Default")
      (node (ref "IC1") (pin "37") (pinfunction "TXD0_37") (pintype "output"))
      (node (ref "IC2") (pin "TXD0") (pinfunction "TXD0_TXD0") (pintype "bidirectional"))
      (node (ref "J_P2") (pin "3") (pinfunction "3_3") (pintype "passive"))
      (node (ref "J_U02T") (pin "1") (pinfunction "1_1") (pintype "passive"))
    )
    (net (code "61") (name "U1RXD") (class "Default")
      (node (ref "GPS") (pin "1") (pinfunction "S_1") (pintype "passive"))
      (node (ref "IC1") (pin "21") (pinfunction "IO18_21") (pintype "bidirectional"))
      (node (ref "IC2") (pin "IO34") (pinfunction "IO34_IO34") (pintype "bidirectional"))
    )
    (net (code "62") (name "U1TXD") (class "Default")
      (node (ref "GPS") (pin "3") (pinfunction "S_3") (pintype "passive"))
      (node (ref "IC1") (pin "20") (pinfunction "IO17_20") (pintype "bidirectional"))
      (node (ref "IC2") (pin "IO32") (pinfunction "IO32_IO32") (pintype "bidirectional"))
    )
    (net (code "63") (name "U2RXD") (class "Default")
      (node (ref "IC1") (pin "12") (pinfunction "IO9_12") (pintype "bidirectional"))
      (node (ref "IC2") (pin "IO35") (pinfunction "IO35_IO35") (pintype "bidirectional"))
      (node (ref "J_U02R") (pin "2") (pinfunction "2_2") (pintype "passive"))
      (node (ref "R33") (pin "2") (pinfunction "2_2") (pintype "passive"))
    )
    (net (code "64") (name "U2TXD") (class "Default")
      (node (ref "D1") (pin "C") (pinfunction "C_C") (pintype "passive"))
      (node (ref "IC1") (pin "10") (pinfunction "IO7_10") (pintype "bidirectional"))
      (node (ref "IC2") (pin "IO33") (pinfunction "IO33_IO33") (pintype "bidirectional"))
      (node (ref "J_U02T") (pin "2") (pinfunction "2_2") (pintype "passive"))
    )
    (net (code "65") (name "U2_BUS") (class "Default")
      (node (ref "D1") (pin "A") (pinfunction "A_A") (pintype "passive"))
      (node (ref "J_L1") (pin "1") (pinfunction "1_1") (pintype "passive"))
      (node (ref "R32") (pin "1") (pinfunction "1_1") (pintype "passive"))
      (node (ref "R33") (pin "1") (pinfunction "1_1") (pintype "passive"))
    )
    (net (code "66") (name "U5") (class "Default")
      (node (ref "I2C") (pin "4") (pinfunction "S_4") (pintype "passive"))
      (node (ref "R") (pin "4") (pinfunction "4_4") (pintype "passive"))
    )
    (net (code "67") (name "UBAT") (class "Default")
      (node (ref "I2C") (pin "6") (pinfunction "S_6") (pintype "passive"))
      (node (ref "R") (pin "5") (pinfunction "5_5") (pintype "passive"))
    )
    (net (code "68") (name "UBUS") (class "Default")
      (node (ref "GPS") (pin "5") (pinfunction "S_5") (pintype "passive"))
      (node (ref "I2C") (pin "2") (pinfunction "S_2") (pintype "passive"))
      (node (ref "J_VCCOUT") (pin "1") (pinfunction "1_1") (pintype "passive"))
      (node (ref "Q2") (pin "3") (pinfunction "D_3") (pintype "passive"))
      (node (ref "SPI") (pin "2") (pinfunction "S_2") (pintype "passive"))
    )
    (net (code "69") (name "USBN") (class "Default")
      (node (ref "C4") (pin "1") (pinfunction "1_1") (pintype "passive"))
      (node (ref "IC1") (pin "22") (pinfunction "IO19_22") (pintype "bidirectional"))
      (node (ref "J_P1") (pin "1") (pinfunction "1_1") (pintype "passive"))
    )
    (net (code "70") (name "USBP") (class "Default")
      (node (ref "C3") (pin "1") (pinfunction "1_1") (pintype "passive"))
      (node (ref "IC1") (pin "23") (pinfunction "IO20_23") (pintype "bidirectional"))
      (node (ref "J_P2") (pin "1") (pinfunction "1_1") (pintype "passive"))
    )
    (net (code "71") (name "VCC") (class "Default")
      (node (ref "C2") (pin "1") (pinfunction "1_1") (pintype "passive"))
      (node (ref "C5") (pin "+") (pinfunction "+_+") (pintype "passive"))
      (node (ref "C6") (pin "+") (pinfunction "+_+") (pintype "passive"))
      (node (ref "IC1") (pin "2") (pinfunction "3V3_2") (pintype "bidirectional"))
      (node (ref "IC2") (pin "VDD33") (pinfunction "3V3_VDD33") (pintype "bidirectional"))
      (node (ref "J_OLED1") (pin "3") (pinfunction "3_3") (pintype "passive"))
      (node (ref "J_OLED2") (pin "3") (pinfunction "3_3") (pintype "passive"))
      (node (ref "J_VCC") (pin "2") (pinfunction "2_2") (pintype "passive"))
      (node (ref "PROG") (pin "3") (pinfunction "S_3") (pintype "passive"))
      (node (ref "Q2") (pin "2") (pinfunction "S_2") (pintype "passive"))
      (node (ref "R10") (pin "2") (pinfunction "2_2") (pintype "passive"))
      (node (ref "R11") (pin "2") (pinfunction "2_2") (pintype "passive"))
      (node (ref "R12") (pin "2") (pinfunction "2_2") (pintype "passive"))
      (node (ref "R13") (pin "2") (pinfunction "2_2") (pintype "passive"))
      (node (ref "R16") (pin "2") (pinfunction "2_2") (pintype "passive"))
      (node (ref "R18") (pin "2") (pinfunction "2_2") (pintype "passive"))
      (node (ref "R25") (pin "1") (pinfunction "1_1") (pintype "passive"))
      (node (ref "R26") (pin "1") (pinfunction "1_1") (pintype "passive"))
      (node (ref "R27") (pin "1") (pinfunction "1_1") (pintype "passive"))
      (node (ref "R28") (pin "1") (pinfunction "1_1") (pintype "passive"))
      (node (ref "R29") (pin "1") (pinfunction "1_1") (pintype "passive"))
      (node (ref "R30") (pin "1") (pinfunction "1_1") (pintype "passive"))
      (node (ref "R31") (pin "1") (pinfunction "1_1") (pintype "passive"))
      (node (ref "R32") (pin "2") (pinfunction "2_2") (pintype "passive"))
      (node (ref "R43") (pin "2") (pinfunction "2_2") (pintype "passive"))
      (node (ref "R45") (pin "1") (pinfunction "1_1") (pintype "passive"))
      (node (ref "R5") (pin "1") (pinfunction "1_1") (pintype "passive"))
      (node (ref "R6") (pin "1") (pinfunction "1_1") (pintype "passive"))
      (node (ref "R7") (pin "1") (pinfunction "1_1") (pintype "passive"))
      (node (ref "R8") (pin "1") (pinfunction "1_1") (pintype "passive"))
      (node (ref "R9") (pin "1") (pinfunction "1_1") (pintype "passive"))
      (node (ref "SDCARD") (pin "4") (pinfunction "VDD_4") (pintype "bidirectional"))
    )
    (net (code "72") (name "unconnected-(BOOT-Pad1)") (class "Default")
      (node (ref "BOOT") (pin "1") (pinfunction "1_1") (pintype "passive"))
    )
    (net (code "73") (name "unconnected-(IC2-NC-PadNC0)") (class "Default")
      (node (ref "IC2") (pin "NC0") (pinfunction "NC_NC0") (pintype "bidirectional"))
    )
    (net (code "74") (name "unconnected-(IC2-PadCLK)") (class "Default")
      (node (ref "IC2") (pin "CLK") (pinfunction "CLK_CLK") (pintype "bidirectional"))
    )
    (net (code "75") (name "unconnected-(IC2-PadCMD)") (class "Default")
      (node (ref "IC2") (pin "CMD") (pinfunction "CMD_CMD") (pintype "bidirectional"))
    )
    (net (code "76") (name "unconnected-(IC2-PadNC1)") (class "Default")
      (node (ref "IC2") (pin "NC1") (pinfunction "NC1_NC1") (pintype "bidirectional"))
    )
    (net (code "77") (name "unconnected-(IC2-PadNC2)") (class "Default")
      (node (ref "IC2") (pin "NC2") (pinfunction "NC2_NC2") (pintype "bidirectional"))
    )
    (net (code "78") (name "unconnected-(IC2-PadSD0)") (class "Default")
      (node (ref "IC2") (pin "SD0") (pinfunction "SD0_SD0") (pintype "bidirectional"))
    )
    (net (code "79") (name "unconnected-(IC2-PadSD1)") (class "Default")
      (node (ref "IC2") (pin "SD1") (pinfunction "SD1_SD1") (pintype "bidirectional"))
    )
    (net (code "80") (name "unconnected-(IC2-PadSD2)") (class "Default")
      (node (ref "IC2") (pin "SD2") (pinfunction "SD2_SD2") (pintype "bidirectional"))
    )
    (net (code "81") (name "unconnected-(IC2-PadSD3)") (class "Default")
      (node (ref "IC2") (pin "SD3") (pinfunction "SD3_SD3") (pintype "bidirectional"))
    )
    (net (code "82") (name "unconnected-(IO13-Pad1)") (class "Default")
      (node (ref "IO13") (pin "1") (pinfunction "1_1") (pintype "passive"))
    )
    (net (code "83") (name "unconnected-(RESET-Pad1)") (class "Default")
      (node (ref "RESET") (pin "1") (pinfunction "1_1") (pintype "passive"))
    )
    (net (code "84") (name "unconnected-(SDCARD-CD(1)-Pad9)") (class "Default")
      (node (ref "SDCARD") (pin "9") (pinfunction "CD(1)_9") (pintype "bidirectional"))
    )
    (net (code "85") (name "unconnected-(SDCARD-CD(2)-Pad10)") (class "Default")
      (node (ref "SDCARD") (pin "10") (pinfunction "CD(2)_10") (pintype "bidirectional"))
    )
  )
)
